# SRAM.net
KiCad netlist of a schematic drawn in EAGLE
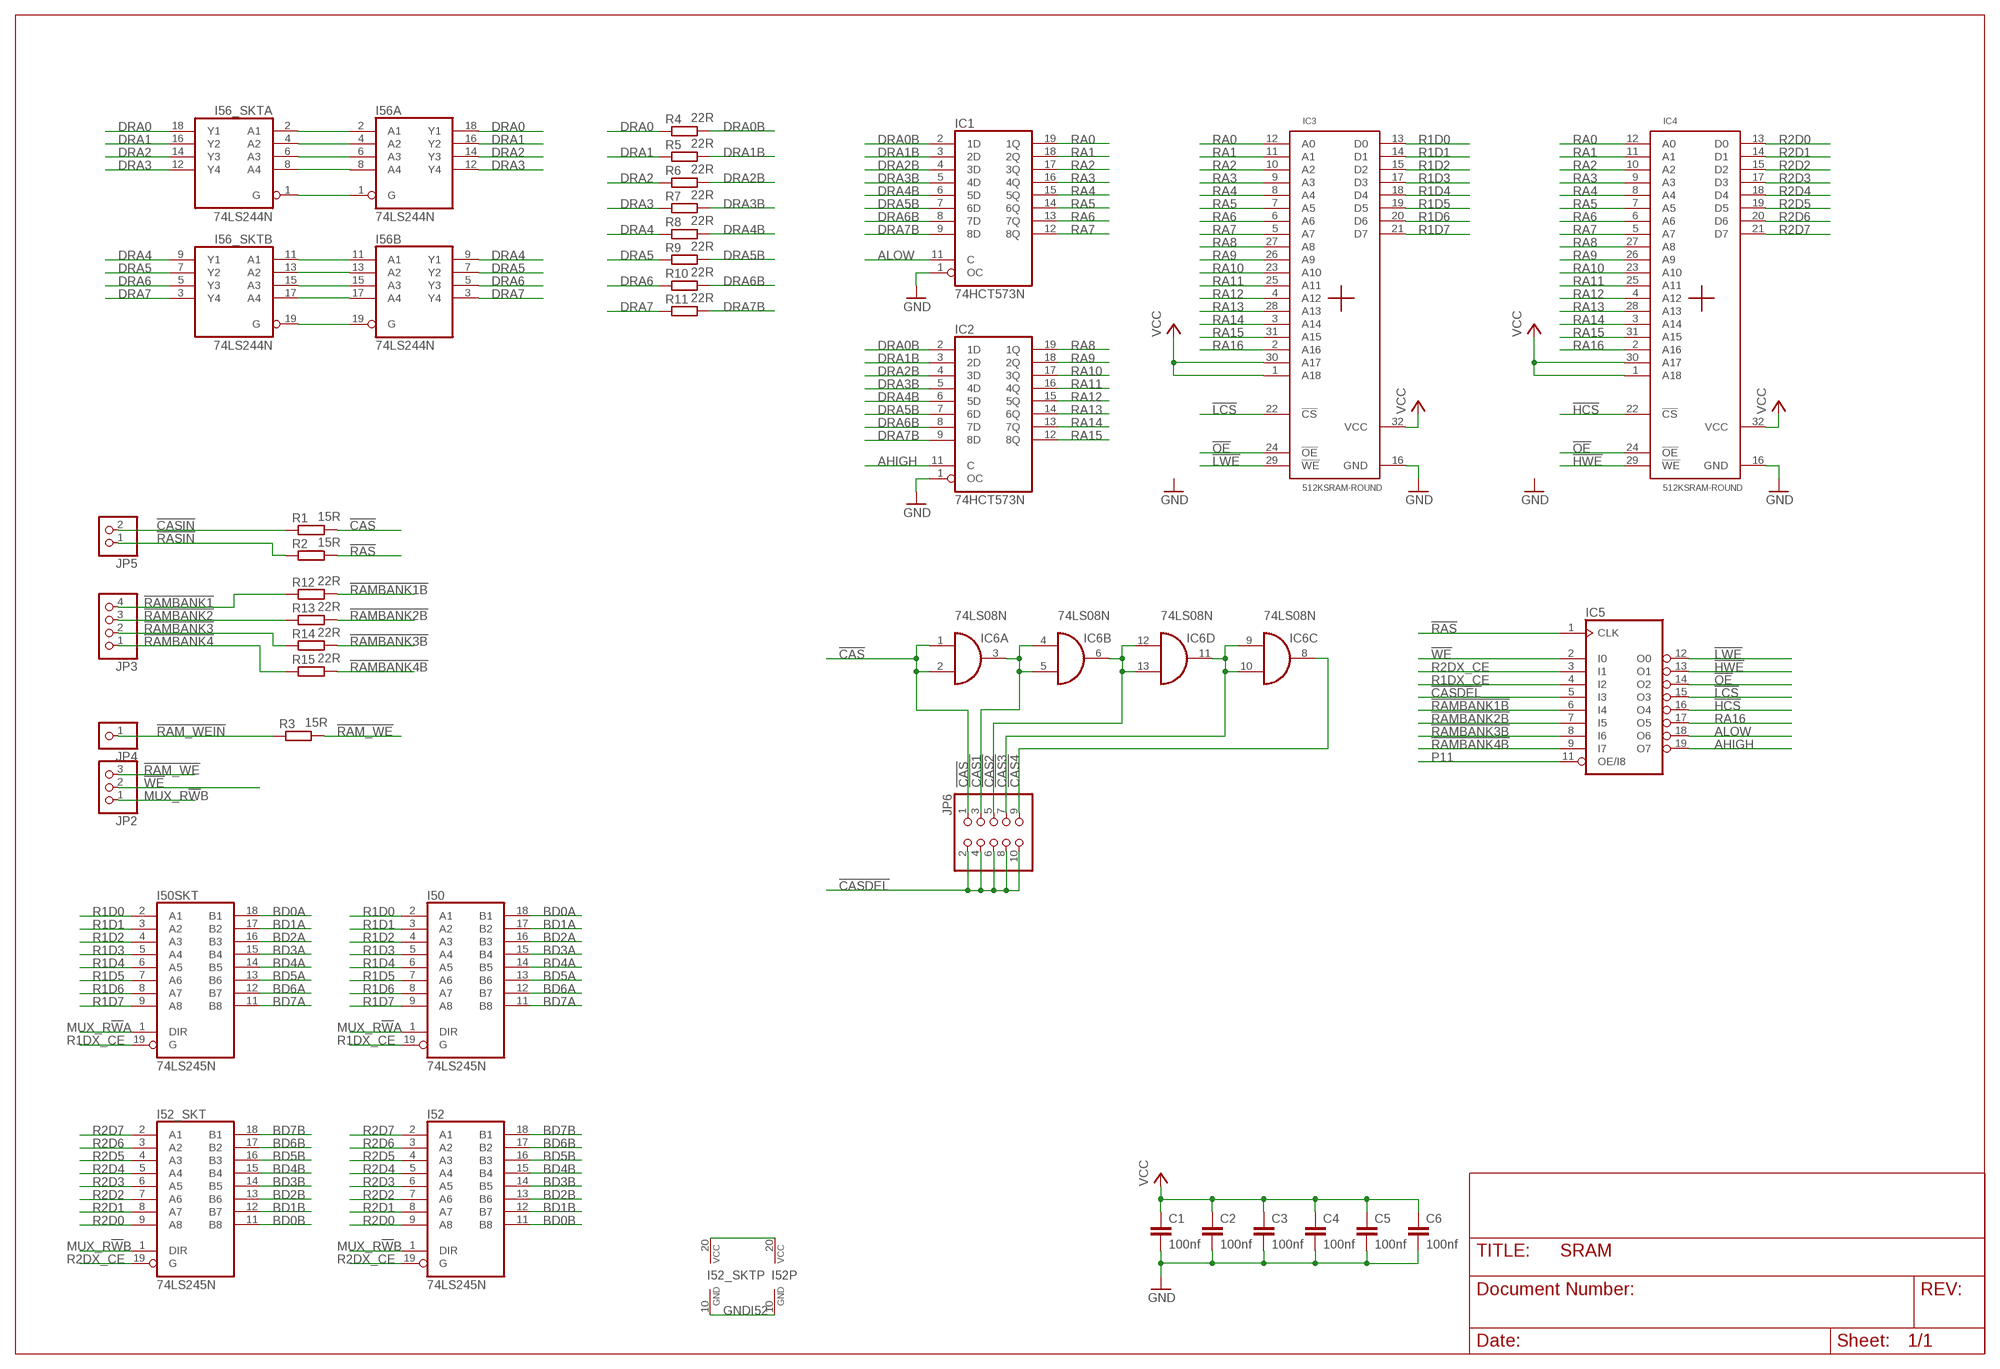
[diagram p0: schematic, sheet 1]

(export (version "E")
  (design (tool "Eeschema 10.0.6"))
  (components
    (comp (ref "C1")
      (value "100nf")
      (footprint "eagle-import:C025-025X050")
      (libsource (lib "eagle-import") (part "C-EU025-025X050"))
    )
    (comp (ref "C2")
      (value "100nf")
      (footprint "eagle-import:C025-025X050")
      (libsource (lib "eagle-import") (part "C-EU025-025X050"))
    )
    (comp (ref "C3")
      (value "100nf")
      (footprint "eagle-import:C025-025X050")
      (libsource (lib "eagle-import") (part "C-EU025-025X050"))
    )
    (comp (ref "C4")
      (value "100nf")
      (footprint "eagle-import:C025-025X050")
      (libsource (lib "eagle-import") (part "C-EU025-025X050"))
    )
    (comp (ref "C5")
      (value "100nf")
      (footprint "eagle-import:C025-025X050")
      (libsource (lib "eagle-import") (part "C-EU025-025X050"))
    )
    (comp (ref "C6")
      (value "100nf")
      (footprint "eagle-import:C025-025X050")
      (libsource (lib "eagle-import") (part "C-EU025-025X050"))
    )
    (comp (ref "I50")
      (value "74LS245N")
      (footprint "eagle-import:DIL20")
      (libsource (lib "eagle-import") (part "74245NLS"))
    )
    (comp (ref "I50SKT")
      (value "74LS245N")
      (footprint "eagle-import:DIL20")
      (libsource (lib "eagle-import") (part "74245NLS"))
    )
    (comp (ref "I52")
      (value "74LS245N")
      (footprint "eagle-import:DIL20")
      (libsource (lib "eagle-import") (part "74245NLS"))
    )
    (comp (ref "I52_SKT")
      (value "74LS245N")
      (footprint "eagle-import:DIL20")
      (libsource (lib "eagle-import") (part "74245NLS"))
    )
    (comp (ref "I56")
      (value "74LS244N")
      (footprint "eagle-import:DIL20")
      (libsource (lib "eagle-import") (part "74244NLS"))
    )
    (comp (ref "I56_SKT")
      (value "74LS244N")
      (footprint "eagle-import:DIL20")
      (libsource (lib "eagle-import") (part "74244NLS"))
    )
    (comp (ref "IC1")
      (value "74HCT573N")
      (footprint "eagle-import:DIL20")
      (libsource (lib "eagle-import") (part "74573NHCT"))
    )
    (comp (ref "IC2")
      (value "74HCT573N")
      (footprint "eagle-import:DIL20")
      (libsource (lib "eagle-import") (part "74573NHCT"))
    )
    (comp (ref "IC3")
      (value "512KSRAM-ROUND")
      (footprint "eagle-import:DIL32-ROUND")
      (libsource (lib "eagle-import") (part "512KSRAM-ROUND"))
    )
    (comp (ref "IC4")
      (value "512KSRAM-ROUND")
      (footprint "eagle-import:DIL32-ROUND")
      (libsource (lib "eagle-import") (part "512KSRAM-ROUND"))
    )
    (comp (ref "IC5")
      (value "16V8-ROUND")
      (footprint "eagle-import:DIL20-R")
      (libsource (lib "eagle-import") (part "16V8-ROUND"))
    )
    (comp (ref "IC6")
      (value "74LS08N")
      (footprint "eagle-import:DIL14")
      (libsource (lib "eagle-import") (part "7408NLS"))
    )
    (comp (ref "JP2")
      (value "PINHD-1X3")
      (footprint "eagle-import:1X03")
      (libsource (lib "eagle-import") (part "PINHD-1X3"))
    )
    (comp (ref "JP3")
      (value "PINHD-1X4")
      (footprint "eagle-import:1X04")
      (libsource (lib "eagle-import") (part "PINHD-1X4"))
    )
    (comp (ref "JP4")
      (value "PINHD-1X1")
      (footprint "eagle-import:1X01")
      (libsource (lib "eagle-import") (part "PINHD-1X1"))
    )
    (comp (ref "JP5")
      (value "PINHD-1X2")
      (footprint "eagle-import:1X02")
      (libsource (lib "eagle-import") (part "PINHD-1X2"))
    )
    (comp (ref "JP6")
      (value "PINHD-2X5")
      (footprint "eagle-import:2X05")
      (libsource (lib "eagle-import") (part "PINHD-2X5"))
    )
    (comp (ref "R1")
      (value "15R")
      (footprint "eagle-import:0204_5")
      (libsource (lib "eagle-import") (part "R-EU_0204/5"))
    )
    (comp (ref "R2")
      (value "15R")
      (footprint "eagle-import:0204_5")
      (libsource (lib "eagle-import") (part "R-EU_0204/5"))
    )
    (comp (ref "R3")
      (value "15R")
      (footprint "eagle-import:0204_5")
      (libsource (lib "eagle-import") (part "R-EU_0204/5"))
    )
    (comp (ref "R4")
      (value "22R")
      (footprint "eagle-import:0204_5")
      (libsource (lib "eagle-import") (part "R-EU_0204/5"))
    )
    (comp (ref "R5")
      (value "22R")
      (footprint "eagle-import:0204_5")
      (libsource (lib "eagle-import") (part "R-EU_0204/5"))
    )
    (comp (ref "R6")
      (value "22R")
      (footprint "eagle-import:0204_5")
      (libsource (lib "eagle-import") (part "R-EU_0204/5"))
    )
    (comp (ref "R7")
      (value "22R")
      (footprint "eagle-import:0204_5")
      (libsource (lib "eagle-import") (part "R-EU_0204/5"))
    )
    (comp (ref "R8")
      (value "22R")
      (footprint "eagle-import:0204_5")
      (libsource (lib "eagle-import") (part "R-EU_0204/5"))
    )
    (comp (ref "R9")
      (value "22R")
      (footprint "eagle-import:0204_5")
      (libsource (lib "eagle-import") (part "R-EU_0204/5"))
    )
    (comp (ref "R10")
      (value "22R")
      (footprint "eagle-import:0204_5")
      (libsource (lib "eagle-import") (part "R-EU_0204/5"))
    )
    (comp (ref "R11")
      (value "22R")
      (footprint "eagle-import:0204_5")
      (libsource (lib "eagle-import") (part "R-EU_0204/5"))
    )
    (comp (ref "R12")
      (value "22R")
      (footprint "eagle-import:0204_5")
      (libsource (lib "eagle-import") (part "R-EU_0204/5"))
    )
    (comp (ref "R13")
      (value "22R")
      (footprint "eagle-import:0204_5")
      (libsource (lib "eagle-import") (part "R-EU_0204/5"))
    )
    (comp (ref "R14")
      (value "22R")
      (footprint "eagle-import:0204_5")
      (libsource (lib "eagle-import") (part "R-EU_0204/5"))
    )
    (comp (ref "R15")
      (value "22R")
      (footprint "eagle-import:0204_5")
      (libsource (lib "eagle-import") (part "R-EU_0204/5"))
    )
  )
  (nets
    (net (code "1") (name "/AHIGH") (class "Default")
      (node (ref "IC2") (pin "11") (pinfunction "C_11") (pintype "input"))
      (node (ref "IC5") (pin "19") (pinfunction "O7_19") (pintype "bidirectional"))
    )
    (net (code "2") (name "/ALOW") (class "Default")
      (node (ref "IC1") (pin "11") (pinfunction "C_11") (pintype "input"))
      (node (ref "IC5") (pin "18") (pinfunction "O6_18") (pintype "bidirectional"))
    )
    (net (code "3") (name "/BD0A") (class "Default")
      (node (ref "I50") (pin "18") (pinfunction "B1_18") (pintype "bidirectional"))
      (node (ref "I50SKT") (pin "18") (pinfunction "B1_18") (pintype "bidirectional"))
    )
    (net (code "4") (name "/BD0B") (class "Default")
      (node (ref "I52") (pin "11") (pinfunction "B8_11") (pintype "bidirectional"))
      (node (ref "I52_SKT") (pin "11") (pinfunction "B8_11") (pintype "bidirectional"))
    )
    (net (code "5") (name "/BD1A") (class "Default")
      (node (ref "I50") (pin "17") (pinfunction "B2_17") (pintype "bidirectional"))
      (node (ref "I50SKT") (pin "17") (pinfunction "B2_17") (pintype "bidirectional"))
    )
    (net (code "6") (name "/BD1B") (class "Default")
      (node (ref "I52") (pin "12") (pinfunction "B7_12") (pintype "bidirectional"))
      (node (ref "I52_SKT") (pin "12") (pinfunction "B7_12") (pintype "bidirectional"))
    )
    (net (code "7") (name "/BD2A") (class "Default")
      (node (ref "I50") (pin "16") (pinfunction "B3_16") (pintype "bidirectional"))
      (node (ref "I50SKT") (pin "16") (pinfunction "B3_16") (pintype "bidirectional"))
    )
    (net (code "8") (name "/BD2B") (class "Default")
      (node (ref "I52") (pin "13") (pinfunction "B6_13") (pintype "bidirectional"))
      (node (ref "I52_SKT") (pin "13") (pinfunction "B6_13") (pintype "bidirectional"))
    )
    (net (code "9") (name "/BD3A") (class "Default")
      (node (ref "I50") (pin "15") (pinfunction "B4_15") (pintype "bidirectional"))
      (node (ref "I50SKT") (pin "15") (pinfunction "B4_15") (pintype "bidirectional"))
    )
    (net (code "10") (name "/BD3B") (class "Default")
      (node (ref "I52") (pin "14") (pinfunction "B5_14") (pintype "bidirectional"))
      (node (ref "I52_SKT") (pin "14") (pinfunction "B5_14") (pintype "bidirectional"))
    )
    (net (code "11") (name "/BD4A") (class "Default")
      (node (ref "I50") (pin "14") (pinfunction "B5_14") (pintype "bidirectional"))
      (node (ref "I50SKT") (pin "14") (pinfunction "B5_14") (pintype "bidirectional"))
    )
    (net (code "12") (name "/BD4B") (class "Default")
      (node (ref "I52") (pin "15") (pinfunction "B4_15") (pintype "bidirectional"))
      (node (ref "I52_SKT") (pin "15") (pinfunction "B4_15") (pintype "bidirectional"))
    )
    (net (code "13") (name "/BD5A") (class "Default")
      (node (ref "I50") (pin "13") (pinfunction "B6_13") (pintype "bidirectional"))
      (node (ref "I50SKT") (pin "13") (pinfunction "B6_13") (pintype "bidirectional"))
    )
    (net (code "14") (name "/BD5B") (class "Default")
      (node (ref "I52") (pin "16") (pinfunction "B3_16") (pintype "bidirectional"))
      (node (ref "I52_SKT") (pin "16") (pinfunction "B3_16") (pintype "bidirectional"))
    )
    (net (code "15") (name "/BD6A") (class "Default")
      (node (ref "I50") (pin "12") (pinfunction "B7_12") (pintype "bidirectional"))
      (node (ref "I50SKT") (pin "12") (pinfunction "B7_12") (pintype "bidirectional"))
    )
    (net (code "16") (name "/BD6B") (class "Default")
      (node (ref "I52") (pin "17") (pinfunction "B2_17") (pintype "bidirectional"))
      (node (ref "I52_SKT") (pin "17") (pinfunction "B2_17") (pintype "bidirectional"))
    )
    (net (code "17") (name "/BD7A") (class "Default")
      (node (ref "I50") (pin "11") (pinfunction "B8_11") (pintype "bidirectional"))
      (node (ref "I50SKT") (pin "11") (pinfunction "B8_11") (pintype "bidirectional"))
    )
    (net (code "18") (name "/BD7B") (class "Default")
      (node (ref "I52") (pin "18") (pinfunction "B1_18") (pintype "bidirectional"))
      (node (ref "I52_SKT") (pin "18") (pinfunction "B1_18") (pintype "bidirectional"))
    )
    (net (code "19") (name "/DRA0") (class "Default")
      (node (ref "I56") (pin "18") (pinfunction "Y1_18") (pintype "tri_state"))
      (node (ref "I56_SKT") (pin "18") (pinfunction "Y1_18") (pintype "tri_state"))
      (node (ref "R4") (pin "1") (pinfunction "1_1") (pintype "passive"))
    )
    (net (code "20") (name "/DRA0B") (class "Default")
      (node (ref "IC1") (pin "2") (pinfunction "1D_2") (pintype "input"))
      (node (ref "IC2") (pin "2") (pinfunction "1D_2") (pintype "input"))
      (node (ref "R4") (pin "2") (pinfunction "2_2") (pintype "passive"))
    )
    (net (code "21") (name "/DRA1") (class "Default")
      (node (ref "I56") (pin "16") (pinfunction "Y2_16") (pintype "tri_state"))
      (node (ref "I56_SKT") (pin "16") (pinfunction "Y2_16") (pintype "tri_state"))
      (node (ref "R5") (pin "1") (pinfunction "1_1") (pintype "passive"))
    )
    (net (code "22") (name "/DRA1B") (class "Default")
      (node (ref "IC1") (pin "3") (pinfunction "2D_3") (pintype "input"))
      (node (ref "IC2") (pin "3") (pinfunction "2D_3") (pintype "input"))
      (node (ref "R5") (pin "2") (pinfunction "2_2") (pintype "passive"))
    )
    (net (code "23") (name "/DRA2") (class "Default")
      (node (ref "I56") (pin "14") (pinfunction "Y3_14") (pintype "tri_state"))
      (node (ref "I56_SKT") (pin "14") (pinfunction "Y3_14") (pintype "tri_state"))
      (node (ref "R6") (pin "1") (pinfunction "1_1") (pintype "passive"))
    )
    (net (code "24") (name "/DRA2B") (class "Default")
      (node (ref "IC1") (pin "4") (pinfunction "3D_4") (pintype "input"))
      (node (ref "IC2") (pin "4") (pinfunction "3D_4") (pintype "input"))
      (node (ref "R6") (pin "2") (pinfunction "2_2") (pintype "passive"))
    )
    (net (code "25") (name "/DRA3") (class "Default")
      (node (ref "I56") (pin "12") (pinfunction "Y4_12") (pintype "tri_state"))
      (node (ref "I56_SKT") (pin "12") (pinfunction "Y4_12") (pintype "tri_state"))
      (node (ref "R7") (pin "1") (pinfunction "1_1") (pintype "passive"))
    )
    (net (code "26") (name "/DRA3B") (class "Default")
      (node (ref "IC1") (pin "5") (pinfunction "4D_5") (pintype "input"))
      (node (ref "IC2") (pin "5") (pinfunction "4D_5") (pintype "input"))
      (node (ref "R7") (pin "2") (pinfunction "2_2") (pintype "passive"))
    )
    (net (code "27") (name "/DRA4") (class "Default")
      (node (ref "I56") (pin "9") (pinfunction "Y1_9") (pintype "tri_state"))
      (node (ref "I56_SKT") (pin "9") (pinfunction "Y1_9") (pintype "tri_state"))
      (node (ref "R8") (pin "1") (pinfunction "1_1") (pintype "passive"))
    )
    (net (code "28") (name "/DRA4B") (class "Default")
      (node (ref "IC1") (pin "6") (pinfunction "5D_6") (pintype "input"))
      (node (ref "IC2") (pin "6") (pinfunction "5D_6") (pintype "input"))
      (node (ref "R8") (pin "2") (pinfunction "2_2") (pintype "passive"))
    )
    (net (code "29") (name "/DRA5") (class "Default")
      (node (ref "I56") (pin "7") (pinfunction "Y2_7") (pintype "tri_state"))
      (node (ref "I56_SKT") (pin "7") (pinfunction "Y2_7") (pintype "tri_state"))
      (node (ref "R9") (pin "1") (pinfunction "1_1") (pintype "passive"))
    )
    (net (code "30") (name "/DRA5B") (class "Default")
      (node (ref "IC1") (pin "7") (pinfunction "6D_7") (pintype "input"))
      (node (ref "IC2") (pin "7") (pinfunction "6D_7") (pintype "input"))
      (node (ref "R9") (pin "2") (pinfunction "2_2") (pintype "passive"))
    )
    (net (code "31") (name "/DRA6") (class "Default")
      (node (ref "I56") (pin "5") (pinfunction "Y3_5") (pintype "tri_state"))
      (node (ref "I56_SKT") (pin "5") (pinfunction "Y3_5") (pintype "tri_state"))
      (node (ref "R10") (pin "1") (pinfunction "1_1") (pintype "passive"))
    )
    (net (code "32") (name "/DRA6B") (class "Default")
      (node (ref "IC1") (pin "8") (pinfunction "7D_8") (pintype "input"))
      (node (ref "IC2") (pin "8") (pinfunction "7D_8") (pintype "input"))
      (node (ref "R10") (pin "2") (pinfunction "2_2") (pintype "passive"))
    )
    (net (code "33") (name "/DRA7") (class "Default")
      (node (ref "I56") (pin "3") (pinfunction "Y4_3") (pintype "tri_state"))
      (node (ref "I56_SKT") (pin "3") (pinfunction "Y4_3") (pintype "tri_state"))
      (node (ref "R11") (pin "1") (pinfunction "1_1") (pintype "passive"))
    )
    (net (code "34") (name "/DRA7B") (class "Default")
      (node (ref "IC1") (pin "9") (pinfunction "8D_9") (pintype "input"))
      (node (ref "IC2") (pin "9") (pinfunction "8D_9") (pintype "input"))
      (node (ref "R11") (pin "2") (pinfunction "2_2") (pintype "passive"))
    )
    (net (code "35") (name "/GNDI52") (class "Default")
      (node (ref "I52") (pin "10") (pinfunction "GND_10") (pintype "power_in"))
      (node (ref "I52_SKT") (pin "10") (pinfunction "GND_10") (pintype "power_in"))
    )
    (net (code "36") (name "/MUX_R~{W}A") (class "Default")
      (node (ref "I50") (pin "1") (pinfunction "DIR_1") (pintype "input"))
      (node (ref "I50SKT") (pin "1") (pinfunction "DIR_1") (pintype "input"))
    )
    (net (code "37") (name "/MUX_R~{W}B") (class "Default")
      (node (ref "I52") (pin "1") (pinfunction "DIR_1") (pintype "input"))
      (node (ref "I52_SKT") (pin "1") (pinfunction "DIR_1") (pintype "input"))
      (node (ref "JP2") (pin "1") (pinfunction "1_1") (pintype "passive"))
    )
    (net (code "38") (name "/P11") (class "Default")
      (node (ref "IC5") (pin "11") (pinfunction "OE/I8_11") (pintype "input"))
    )
    (net (code "39") (name "/R1D0") (class "Default")
      (node (ref "I50") (pin "2") (pinfunction "A1_2") (pintype "bidirectional"))
      (node (ref "I50SKT") (pin "2") (pinfunction "A1_2") (pintype "bidirectional"))
      (node (ref "IC3") (pin "13") (pinfunction "D0_13") (pintype "bidirectional"))
    )
    (net (code "40") (name "/R1D1") (class "Default")
      (node (ref "I50") (pin "3") (pinfunction "A2_3") (pintype "bidirectional"))
      (node (ref "I50SKT") (pin "3") (pinfunction "A2_3") (pintype "bidirectional"))
      (node (ref "IC3") (pin "14") (pinfunction "D1_14") (pintype "bidirectional"))
    )
    (net (code "41") (name "/R1D2") (class "Default")
      (node (ref "I50") (pin "4") (pinfunction "A3_4") (pintype "bidirectional"))
      (node (ref "I50SKT") (pin "4") (pinfunction "A3_4") (pintype "bidirectional"))
      (node (ref "IC3") (pin "15") (pinfunction "D2_15") (pintype "bidirectional"))
    )
    (net (code "42") (name "/R1D3") (class "Default")
      (node (ref "I50") (pin "5") (pinfunction "A4_5") (pintype "bidirectional"))
      (node (ref "I50SKT") (pin "5") (pinfunction "A4_5") (pintype "bidirectional"))
      (node (ref "IC3") (pin "17") (pinfunction "D3_17") (pintype "bidirectional"))
    )
    (net (code "43") (name "/R1D4") (class "Default")
      (node (ref "I50") (pin "6") (pinfunction "A5_6") (pintype "bidirectional"))
      (node (ref "I50SKT") (pin "6") (pinfunction "A5_6") (pintype "bidirectional"))
      (node (ref "IC3") (pin "18") (pinfunction "D4_18") (pintype "bidirectional"))
    )
    (net (code "44") (name "/R1D5") (class "Default")
      (node (ref "I50") (pin "7") (pinfunction "A6_7") (pintype "bidirectional"))
      (node (ref "I50SKT") (pin "7") (pinfunction "A6_7") (pintype "bidirectional"))
      (node (ref "IC3") (pin "19") (pinfunction "D5_19") (pintype "bidirectional"))
    )
    (net (code "45") (name "/R1D6") (class "Default")
      (node (ref "I50") (pin "8") (pinfunction "A7_8") (pintype "bidirectional"))
      (node (ref "I50SKT") (pin "8") (pinfunction "A7_8") (pintype "bidirectional"))
      (node (ref "IC3") (pin "20") (pinfunction "D6_20") (pintype "bidirectional"))
    )
    (net (code "46") (name "/R1D7") (class "Default")
      (node (ref "I50") (pin "9") (pinfunction "A8_9") (pintype "bidirectional"))
      (node (ref "I50SKT") (pin "9") (pinfunction "A8_9") (pintype "bidirectional"))
      (node (ref "IC3") (pin "21") (pinfunction "D7_21") (pintype "bidirectional"))
    )
    (net (code "47") (name "/R1DX_CE") (class "Default")
      (node (ref "I50") (pin "19") (pinfunction "G_19") (pintype "input"))
      (node (ref "I50SKT") (pin "19") (pinfunction "G_19") (pintype "input"))
      (node (ref "IC5") (pin "4") (pinfunction "I2_4") (pintype "input"))
    )
    (net (code "48") (name "/R2D0") (class "Default")
      (node (ref "I52") (pin "9") (pinfunction "A8_9") (pintype "bidirectional"))
      (node (ref "I52_SKT") (pin "9") (pinfunction "A8_9") (pintype "bidirectional"))
      (node (ref "IC4") (pin "13") (pinfunction "D0_13") (pintype "bidirectional"))
    )
    (net (code "49") (name "/R2D1") (class "Default")
      (node (ref "I52") (pin "8") (pinfunction "A7_8") (pintype "bidirectional"))
      (node (ref "I52_SKT") (pin "8") (pinfunction "A7_8") (pintype "bidirectional"))
      (node (ref "IC4") (pin "14") (pinfunction "D1_14") (pintype "bidirectional"))
    )
    (net (code "50") (name "/R2D2") (class "Default")
      (node (ref "I52") (pin "7") (pinfunction "A6_7") (pintype "bidirectional"))
      (node (ref "I52_SKT") (pin "7") (pinfunction "A6_7") (pintype "bidirectional"))
      (node (ref "IC4") (pin "15") (pinfunction "D2_15") (pintype "bidirectional"))
    )
    (net (code "51") (name "/R2D3") (class "Default")
      (node (ref "I52") (pin "6") (pinfunction "A5_6") (pintype "bidirectional"))
      (node (ref "I52_SKT") (pin "6") (pinfunction "A5_6") (pintype "bidirectional"))
      (node (ref "IC4") (pin "17") (pinfunction "D3_17") (pintype "bidirectional"))
    )
    (net (code "52") (name "/R2D4") (class "Default")
      (node (ref "I52") (pin "5") (pinfunction "A4_5") (pintype "bidirectional"))
      (node (ref "I52_SKT") (pin "5") (pinfunction "A4_5") (pintype "bidirectional"))
      (node (ref "IC4") (pin "18") (pinfunction "D4_18") (pintype "bidirectional"))
    )
    (net (code "53") (name "/R2D5") (class "Default")
      (node (ref "I52") (pin "4") (pinfunction "A3_4") (pintype "bidirectional"))
      (node (ref "I52_SKT") (pin "4") (pinfunction "A3_4") (pintype "bidirectional"))
      (node (ref "IC4") (pin "19") (pinfunction "D5_19") (pintype "bidirectional"))
    )
    (net (code "54") (name "/R2D6") (class "Default")
      (node (ref "I52") (pin "3") (pinfunction "A2_3") (pintype "bidirectional"))
      (node (ref "I52_SKT") (pin "3") (pinfunction "A2_3") (pintype "bidirectional"))
      (node (ref "IC4") (pin "20") (pinfunction "D6_20") (pintype "bidirectional"))
    )
    (net (code "55") (name "/R2D7") (class "Default")
      (node (ref "I52") (pin "2") (pinfunction "A1_2") (pintype "bidirectional"))
      (node (ref "I52_SKT") (pin "2") (pinfunction "A1_2") (pintype "bidirectional"))
      (node (ref "IC4") (pin "21") (pinfunction "D7_21") (pintype "bidirectional"))
    )
    (net (code "56") (name "/R2DX_CE") (class "Default")
      (node (ref "I52") (pin "19") (pinfunction "G_19") (pintype "input"))
      (node (ref "I52_SKT") (pin "19") (pinfunction "G_19") (pintype "input"))
      (node (ref "IC5") (pin "3") (pinfunction "I1_3") (pintype "input"))
    )
    (net (code "57") (name "/RA0") (class "Default")
      (node (ref "IC1") (pin "19") (pinfunction "1Q_19") (pintype "tri_state"))
      (node (ref "IC3") (pin "12") (pinfunction "A0_12") (pintype "input"))
      (node (ref "IC4") (pin "12") (pinfunction "A0_12") (pintype "input"))
    )
    (net (code "58") (name "/RA1") (class "Default")
      (node (ref "IC1") (pin "18") (pinfunction "2Q_18") (pintype "tri_state"))
      (node (ref "IC3") (pin "11") (pinfunction "A1_11") (pintype "input"))
      (node (ref "IC4") (pin "11") (pinfunction "A1_11") (pintype "input"))
    )
    (net (code "59") (name "/RA2") (class "Default")
      (node (ref "IC1") (pin "17") (pinfunction "3Q_17") (pintype "tri_state"))
      (node (ref "IC3") (pin "10") (pinfunction "A2_10") (pintype "input"))
      (node (ref "IC4") (pin "10") (pinfunction "A2_10") (pintype "input"))
    )
    (net (code "60") (name "/RA3") (class "Default")
      (node (ref "IC1") (pin "16") (pinfunction "4Q_16") (pintype "tri_state"))
      (node (ref "IC3") (pin "9") (pinfunction "A3_9") (pintype "input"))
      (node (ref "IC4") (pin "9") (pinfunction "A3_9") (pintype "input"))
    )
    (net (code "61") (name "/RA4") (class "Default")
      (node (ref "IC1") (pin "15") (pinfunction "5Q_15") (pintype "tri_state"))
      (node (ref "IC3") (pin "8") (pinfunction "A4_8") (pintype "input"))
      (node (ref "IC4") (pin "8") (pinfunction "A4_8") (pintype "input"))
    )
    (net (code "62") (name "/RA5") (class "Default")
      (node (ref "IC1") (pin "14") (pinfunction "6Q_14") (pintype "tri_state"))
      (node (ref "IC3") (pin "7") (pinfunction "A5_7") (pintype "input"))
      (node (ref "IC4") (pin "7") (pinfunction "A5_7") (pintype "input"))
    )
    (net (code "63") (name "/RA6") (class "Default")
      (node (ref "IC1") (pin "13") (pinfunction "7Q_13") (pintype "tri_state"))
      (node (ref "IC3") (pin "6") (pinfunction "A6_6") (pintype "input"))
      (node (ref "IC4") (pin "6") (pinfunction "A6_6") (pintype "input"))
    )
    (net (code "64") (name "/RA7") (class "Default")
      (node (ref "IC1") (pin "12") (pinfunction "8Q_12") (pintype "tri_state"))
      (node (ref "IC3") (pin "5") (pinfunction "A7_5") (pintype "input"))
      (node (ref "IC4") (pin "5") (pinfunction "A7_5") (pintype "input"))
    )
    (net (code "65") (name "/RA8") (class "Default")
      (node (ref "IC2") (pin "19") (pinfunction "1Q_19") (pintype "tri_state"))
      (node (ref "IC3") (pin "27") (pinfunction "A8_27") (pintype "input"))
      (node (ref "IC4") (pin "27") (pinfunction "A8_27") (pintype "input"))
    )
    (net (code "66") (name "/RA9") (class "Default")
      (node (ref "IC2") (pin "18") (pinfunction "2Q_18") (pintype "tri_state"))
      (node (ref "IC3") (pin "26") (pinfunction "A9_26") (pintype "input"))
      (node (ref "IC4") (pin "26") (pinfunction "A9_26") (pintype "input"))
    )
    (net (code "67") (name "/RA10") (class "Default")
      (node (ref "IC2") (pin "17") (pinfunction "3Q_17") (pintype "tri_state"))
      (node (ref "IC3") (pin "23") (pinfunction "A10_23") (pintype "input"))
      (node (ref "IC4") (pin "23") (pinfunction "A10_23") (pintype "input"))
    )
    (net (code "68") (name "/RA11") (class "Default")
      (node (ref "IC2") (pin "16") (pinfunction "4Q_16") (pintype "tri_state"))
      (node (ref "IC3") (pin "25") (pinfunction "A11_25") (pintype "input"))
      (node (ref "IC4") (pin "25") (pinfunction "A11_25") (pintype "input"))
    )
    (net (code "69") (name "/RA12") (class "Default")
      (node (ref "IC2") (pin "15") (pinfunction "5Q_15") (pintype "tri_state"))
      (node (ref "IC3") (pin "4") (pinfunction "A12_4") (pintype "input"))
      (node (ref "IC4") (pin "4") (pinfunction "A12_4") (pintype "input"))
    )
    (net (code "70") (name "/RA13") (class "Default")
      (node (ref "IC2") (pin "14") (pinfunction "6Q_14") (pintype "tri_state"))
      (node (ref "IC3") (pin "28") (pinfunction "A13_28") (pintype "input"))
      (node (ref "IC4") (pin "28") (pinfunction "A13_28") (pintype "input"))
    )
    (net (code "71") (name "/RA14") (class "Default")
      (node (ref "IC2") (pin "13") (pinfunction "7Q_13") (pintype "tri_state"))
      (node (ref "IC3") (pin "3") (pinfunction "A14_3") (pintype "input"))
      (node (ref "IC4") (pin "3") (pinfunction "A14_3") (pintype "input"))
    )
    (net (code "72") (name "/RA15") (class "Default")
      (node (ref "IC2") (pin "12") (pinfunction "8Q_12") (pintype "tri_state"))
      (node (ref "IC3") (pin "31") (pinfunction "A15_31") (pintype "input"))
      (node (ref "IC4") (pin "31") (pinfunction "A15_31") (pintype "input"))
    )
    (net (code "73") (name "/RA16") (class "Default")
      (node (ref "IC3") (pin "2") (pinfunction "A16_2") (pintype "input"))
      (node (ref "IC4") (pin "2") (pinfunction "A16_2") (pintype "input"))
      (node (ref "IC5") (pin "17") (pinfunction "O5_17") (pintype "bidirectional"))
    )
    (net (code "74") (name "/~{CAS1}") (class "Default")
      (node (ref "IC6") (pin "3") (pinfunction "O_3") (pintype "output"))
      (node (ref "IC6") (pin "4") (pinfunction "I0_4") (pintype "input"))
      (node (ref "IC6") (pin "5") (pinfunction "I1_5") (pintype "input"))
      (node (ref "JP6") (pin "3") (pinfunction "3_3") (pintype "passive"))
    )
    (net (code "75") (name "/~{CAS2}") (class "Default")
      (node (ref "IC6") (pin "12") (pinfunction "I0_12") (pintype "input"))
      (node (ref "IC6") (pin "13") (pinfunction "I1_13") (pintype "input"))
      (node (ref "IC6") (pin "6") (pinfunction "O_6") (pintype "output"))
      (node (ref "JP6") (pin "5") (pinfunction "5_5") (pintype "passive"))
    )
    (net (code "76") (name "/~{CAS3}") (class "Default")
      (node (ref "IC6") (pin "10") (pinfunction "I1_10") (pintype "input"))
      (node (ref "IC6") (pin "11") (pinfunction "O_11") (pintype "output"))
      (node (ref "IC6") (pin "9") (pinfunction "I0_9") (pintype "input"))
      (node (ref "JP6") (pin "7") (pinfunction "7_7") (pintype "passive"))
    )
    (net (code "77") (name "/~{CAS4}") (class "Default")
      (node (ref "IC6") (pin "8") (pinfunction "O_8") (pintype "output"))
      (node (ref "JP6") (pin "9") (pinfunction "9_9") (pintype "passive"))
    )
    (net (code "78") (name "/~{CASDEL}") (class "Default")
      (node (ref "IC5") (pin "5") (pinfunction "I3_5") (pintype "input"))
      (node (ref "JP6") (pin "10") (pinfunction "10_10") (pintype "passive"))
      (node (ref "JP6") (pin "2") (pinfunction "2_2") (pintype "passive"))
      (node (ref "JP6") (pin "4") (pinfunction "4_4") (pintype "passive"))
      (node (ref "JP6") (pin "6") (pinfunction "6_6") (pintype "passive"))
      (node (ref "JP6") (pin "8") (pinfunction "8_8") (pintype "passive"))
    )
    (net (code "79") (name "/~{CASIN}") (class "Default")
      (node (ref "JP5") (pin "2") (pinfunction "2_2") (pintype "passive"))
      (node (ref "R1") (pin "1") (pinfunction "1_1") (pintype "passive"))
    )
    (net (code "80") (name "/~{CAS}") (class "Default")
      (node (ref "IC6") (pin "1") (pinfunction "I0_1") (pintype "input"))
      (node (ref "IC6") (pin "2") (pinfunction "I1_2") (pintype "input"))
      (node (ref "JP6") (pin "1") (pinfunction "1_1") (pintype "passive"))
      (node (ref "R1") (pin "2") (pinfunction "2_2") (pintype "passive"))
    )
    (net (code "81") (name "/~{HCS}") (class "Default")
      (node (ref "IC4") (pin "22") (pinfunction "~{CS}_22") (pintype "input"))
      (node (ref "IC5") (pin "16") (pinfunction "O4_16") (pintype "bidirectional"))
    )
    (net (code "82") (name "/~{HWE}") (class "Default")
      (node (ref "IC4") (pin "29") (pinfunction "~{WE}_29") (pintype "input"))
      (node (ref "IC5") (pin "13") (pinfunction "O1_13") (pintype "bidirectional"))
    )
    (net (code "83") (name "/~{LCS}") (class "Default")
      (node (ref "IC3") (pin "22") (pinfunction "~{CS}_22") (pintype "input"))
      (node (ref "IC5") (pin "15") (pinfunction "O3_15") (pintype "bidirectional"))
    )
    (net (code "84") (name "/~{LWE}") (class "Default")
      (node (ref "IC3") (pin "29") (pinfunction "~{WE}_29") (pintype "input"))
      (node (ref "IC5") (pin "12") (pinfunction "O0_12") (pintype "bidirectional"))
    )
    (net (code "85") (name "/~{OE}") (class "Default")
      (node (ref "IC3") (pin "24") (pinfunction "~{OE}_24") (pintype "input"))
      (node (ref "IC4") (pin "24") (pinfunction "~{OE}_24") (pintype "input"))
      (node (ref "IC5") (pin "14") (pinfunction "O2_14") (pintype "bidirectional"))
    )
    (net (code "86") (name "/~{RAMBANK1B}") (class "Default")
      (node (ref "IC5") (pin "6") (pinfunction "I4_6") (pintype "input"))
      (node (ref "R12") (pin "2") (pinfunction "2_2") (pintype "passive"))
    )
    (net (code "87") (name "/~{RAMBANK1}") (class "Default")
      (node (ref "JP3") (pin "4") (pinfunction "4_4") (pintype "passive"))
      (node (ref "R12") (pin "1") (pinfunction "1_1") (pintype "passive"))
    )
    (net (code "88") (name "/~{RAMBANK2B}") (class "Default")
      (node (ref "IC5") (pin "7") (pinfunction "I5_7") (pintype "input"))
      (node (ref "R13") (pin "2") (pinfunction "2_2") (pintype "passive"))
    )
    (net (code "89") (name "/~{RAMBANK2}") (class "Default")
      (node (ref "JP3") (pin "3") (pinfunction "3_3") (pintype "passive"))
      (node (ref "R13") (pin "1") (pinfunction "1_1") (pintype "passive"))
    )
    (net (code "90") (name "/~{RAMBANK3B}") (class "Default")
      (node (ref "IC5") (pin "8") (pinfunction "I6_8") (pintype "input"))
      (node (ref "R14") (pin "2") (pinfunction "2_2") (pintype "passive"))
    )
    (net (code "91") (name "/~{RAMBANK3}") (class "Default")
      (node (ref "JP3") (pin "2") (pinfunction "2_2") (pintype "passive"))
      (node (ref "R14") (pin "1") (pinfunction "1_1") (pintype "passive"))
    )
    (net (code "92") (name "/~{RAMBANK4B}") (class "Default")
      (node (ref "IC5") (pin "9") (pinfunction "I7_9") (pintype "input"))
      (node (ref "R15") (pin "2") (pinfunction "2_2") (pintype "passive"))
    )
    (net (code "93") (name "/~{RAMBANK4}") (class "Default")
      (node (ref "JP3") (pin "1") (pinfunction "1_1") (pintype "passive"))
      (node (ref "R15") (pin "1") (pinfunction "1_1") (pintype "passive"))
    )
    (net (code "94") (name "/~{RAM_WEIN}") (class "Default")
      (node (ref "JP4") (pin "1") (pinfunction "1_1") (pintype "passive"))
      (node (ref "R3") (pin "1") (pinfunction "1_1") (pintype "passive"))
    )
    (net (code "95") (name "/~{RAM_WE}") (class "Default")
      (node (ref "JP2") (pin "3") (pinfunction "3_3") (pintype "passive"))
      (node (ref "R3") (pin "2") (pinfunction "2_2") (pintype "passive"))
    )
    (net (code "96") (name "/~{RASIN}") (class "Default")
      (node (ref "JP5") (pin "1") (pinfunction "1_1") (pintype "passive"))
      (node (ref "R2") (pin "1") (pinfunction "1_1") (pintype "passive"))
    )
    (net (code "97") (name "/~{RAS}") (class "Default")
      (node (ref "IC5") (pin "1") (pinfunction "CLK_1") (pintype "input"))
      (node (ref "R2") (pin "2") (pinfunction "2_2") (pintype "passive"))
    )
    (net (code "98") (name "/~{WE}") (class "Default")
      (node (ref "IC5") (pin "2") (pinfunction "I0_2") (pintype "input"))
      (node (ref "JP2") (pin "2") (pinfunction "2_2") (pintype "passive"))
    )
    (net (code "99") (name "GND") (class "Default")
      (node (ref "C1") (pin "2") (pinfunction "2_2") (pintype "passive"))
      (node (ref "C2") (pin "2") (pinfunction "2_2") (pintype "passive"))
      (node (ref "C3") (pin "2") (pinfunction "2_2") (pintype "passive"))
      (node (ref "C4") (pin "2") (pinfunction "2_2") (pintype "passive"))
      (node (ref "C5") (pin "2") (pinfunction "2_2") (pintype "passive"))
      (node (ref "C6") (pin "2") (pinfunction "2_2") (pintype "passive"))
      (node (ref "IC1") (pin "1") (pinfunction "OC_1") (pintype "input"))
      (node (ref "IC2") (pin "1") (pinfunction "OC_1") (pintype "input"))
      (node (ref "IC3") (pin "16") (pinfunction "GND_16") (pintype "power_in"))
      (node (ref "IC4") (pin "16") (pinfunction "GND_16") (pintype "power_in"))
    )
    (net (code "100") (name "Net-(I52B-VCC)") (class "Default")
      (node (ref "I52") (pin "20") (pinfunction "VCC_20") (pintype "power_in"))
      (node (ref "I52_SKT") (pin "20") (pinfunction "VCC_20") (pintype "power_in"))
    )
    (net (code "101") (name "Net-(I56A-A1)") (class "Default")
      (node (ref "I56") (pin "2") (pinfunction "A1_2") (pintype "input"))
      (node (ref "I56_SKT") (pin "2") (pinfunction "A1_2") (pintype "input"))
    )
    (net (code "102") (name "Net-(I56A-A2)") (class "Default")
      (node (ref "I56") (pin "4") (pinfunction "A2_4") (pintype "input"))
      (node (ref "I56_SKT") (pin "4") (pinfunction "A2_4") (pintype "input"))
    )
    (net (code "103") (name "Net-(I56A-A3)") (class "Default")
      (node (ref "I56") (pin "6") (pinfunction "A3_6") (pintype "input"))
      (node (ref "I56_SKT") (pin "6") (pinfunction "A3_6") (pintype "input"))
    )
    (net (code "104") (name "Net-(I56A-A4)") (class "Default")
      (node (ref "I56") (pin "8") (pinfunction "A4_8") (pintype "input"))
      (node (ref "I56_SKT") (pin "8") (pinfunction "A4_8") (pintype "input"))
    )
    (net (code "105") (name "Net-(I56A-G)") (class "Default")
      (node (ref "I56") (pin "1") (pinfunction "G_1") (pintype "input"))
      (node (ref "I56_SKT") (pin "1") (pinfunction "G_1") (pintype "input"))
    )
    (net (code "106") (name "Net-(I56B-A1)") (class "Default")
      (node (ref "I56") (pin "11") (pinfunction "A1_11") (pintype "input"))
      (node (ref "I56_SKT") (pin "11") (pinfunction "A1_11") (pintype "input"))
    )
    (net (code "107") (name "Net-(I56B-A2)") (class "Default")
      (node (ref "I56") (pin "13") (pinfunction "A2_13") (pintype "input"))
      (node (ref "I56_SKT") (pin "13") (pinfunction "A2_13") (pintype "input"))
    )
    (net (code "108") (name "Net-(I56B-A3)") (class "Default")
      (node (ref "I56") (pin "15") (pinfunction "A3_15") (pintype "input"))
      (node (ref "I56_SKT") (pin "15") (pinfunction "A3_15") (pintype "input"))
    )
    (net (code "109") (name "Net-(I56B-A4)") (class "Default")
      (node (ref "I56") (pin "17") (pinfunction "A4_17") (pintype "input"))
      (node (ref "I56_SKT") (pin "17") (pinfunction "A4_17") (pintype "input"))
    )
    (net (code "110") (name "Net-(I56B-G)") (class "Default")
      (node (ref "I56") (pin "19") (pinfunction "G_19") (pintype "input"))
      (node (ref "I56_SKT") (pin "19") (pinfunction "G_19") (pintype "input"))
    )
    (net (code "111") (name "VCC") (class "Default")
      (node (ref "C1") (pin "1") (pinfunction "1_1") (pintype "passive"))
      (node (ref "C2") (pin "1") (pinfunction "1_1") (pintype "passive"))
      (node (ref "C3") (pin "1") (pinfunction "1_1") (pintype "passive"))
      (node (ref "C4") (pin "1") (pinfunction "1_1") (pintype "passive"))
      (node (ref "C5") (pin "1") (pinfunction "1_1") (pintype "passive"))
      (node (ref "C6") (pin "1") (pinfunction "1_1") (pintype "passive"))
      (node (ref "IC3") (pin "1") (pinfunction "A18_1") (pintype "input"))
      (node (ref "IC3") (pin "30") (pinfunction "A17_30") (pintype "input"))
      (node (ref "IC3") (pin "32") (pinfunction "VCC_32") (pintype "power_in"))
      (node (ref "IC4") (pin "1") (pinfunction "A18_1") (pintype "input"))
      (node (ref "IC4") (pin "30") (pinfunction "A17_30") (pintype "input"))
      (node (ref "IC4") (pin "32") (pinfunction "VCC_32") (pintype "power_in"))
    )
  )
)
